# GasAlarm.net
KiCad netlist of a schematic drawn in EAGLE
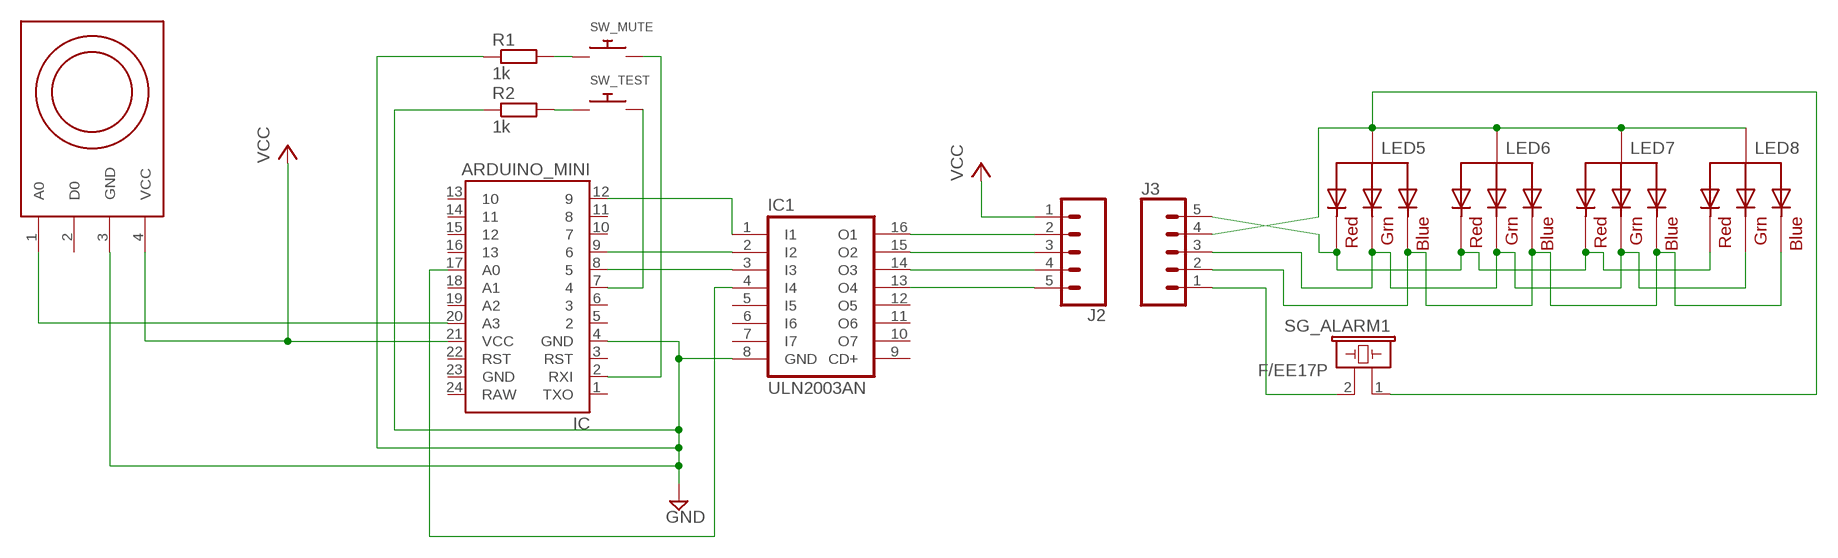
[diagram p0: schematic, sheet 1]

(export (version "E")
  (design (tool "Eeschema 10.0.6"))
  (components
    (comp (ref "IC")
      (value "ARDUINO_MINI")
      (footprint "eagle-import:ARDUINO_MINI")
      (libsource (lib "eagle-import") (part "ARDUINO_MINI"))
    )
    (comp (ref "IC1")
      (value "ULN2003AN")
      (footprint "eagle-import:DIL16")
      (libsource (lib "eagle-import") (part "ULN2003AN"))
    )
    (comp (ref "J2")
      (value "CONN_05")
      (footprint "eagle-import:1X05")
      (libsource (lib "eagle-import") (part "CONN_05"))
    )
    (comp (ref "J3")
      (value "CONN_05")
      (footprint "eagle-import:1X05")
      (libsource (lib "eagle-import") (part "CONN_05"))
    )
    (comp (ref "LED5")
      (value "RGBLED_CA-5MM")
      (footprint "eagle-import:LED5MMRGB")
      (libsource (lib "eagle-import") (part "RGBLED_CA-5MM"))
    )
    (comp (ref "LED6")
      (value "RGBLED_CA-5MM")
      (footprint "eagle-import:LED5MMRGB")
      (libsource (lib "eagle-import") (part "RGBLED_CA-5MM"))
    )
    (comp (ref "LED7")
      (value "RGBLED_CA-5MM")
      (footprint "eagle-import:LED5MMRGB")
      (libsource (lib "eagle-import") (part "RGBLED_CA-5MM"))
    )
    (comp (ref "LED8")
      (value "RGBLED_CA-5MM")
      (footprint "eagle-import:LED5MMRGB")
      (libsource (lib "eagle-import") (part "RGBLED_CA-5MM"))
    )
    (comp (ref "MQ6")
      (value "MQ-6")
      (footprint "eagle-import:DIP4-MQ_6")
      (libsource (lib "eagle-import") (part "MQ-6"))
    )
    (comp (ref "R1")
      (value "1k")
      (footprint "eagle-import:0204_5")
      (libsource (lib "eagle-import") (part "R-EU_0204/5"))
    )
    (comp (ref "R2")
      (value "1k")
      (footprint "eagle-import:0204_5")
      (libsource (lib "eagle-import") (part "R-EU_0204/5"))
    )
    (comp (ref "SG_ALARM1")
      (value "F/EE17P")
      (footprint "eagle-import:F_EE17P")
      (libsource (lib "eagle-import") (part "F/EE17P"))
    )
    (comp (ref "SW_MUTE")
      (value "SWITCH_PUSHBUTTONSOFTTOUCHSMD_SJ")
      (footprint "eagle-import:PUSHBUTTON_SMD_SJ")
      (libsource (lib "eagle-import") (part "SWITCH_PUSHBUTTONSOFTTOUCHSMD_SJ"))
    )
    (comp (ref "SW_TEST")
      (value "SWITCH_PUSHBUTTONSOFTTOUCHSMD_SJ")
      (footprint "eagle-import:PUSHBUTTON_SMD_SJ")
      (libsource (lib "eagle-import") (part "SWITCH_PUSHBUTTONSOFTTOUCHSMD_SJ"))
    )
  )
  (nets
    (net (code "1") (name "GND") (class "Default")
      (node (ref "IC") (pin "4") (pinfunction "GND_4") (pintype "bidirectional"))
      (node (ref "IC1") (pin "8") (pinfunction "GND_8") (pintype "power_in"))
      (node (ref "MQ6") (pin "3") (pinfunction "GND_3") (pintype "bidirectional"))
      (node (ref "R1") (pin "1") (pinfunction "1_1") (pintype "passive"))
      (node (ref "R2") (pin "1") (pinfunction "1_1") (pintype "passive"))
    )
    (net (code "2") (name "Net-(IC-4)") (class "Default")
      (node (ref "IC") (pin "7") (pinfunction "4_7") (pintype "bidirectional"))
      (node (ref "SW_TEST") (pin "P$2") (pinfunction "P$2_P$2") (pintype "passive"))
    )
    (net (code "3") (name "Net-(IC-5)") (class "Default")
      (node (ref "IC") (pin "8") (pinfunction "5_8") (pintype "bidirectional"))
      (node (ref "IC1") (pin "3") (pinfunction "I3_3") (pintype "input"))
    )
    (net (code "4") (name "Net-(IC-6)") (class "Default")
      (node (ref "IC") (pin "9") (pinfunction "6_9") (pintype "bidirectional"))
      (node (ref "IC1") (pin "2") (pinfunction "I2_2") (pintype "input"))
    )
    (net (code "5") (name "Net-(IC-9)") (class "Default")
      (node (ref "IC") (pin "12") (pinfunction "9_12") (pintype "bidirectional"))
      (node (ref "IC1") (pin "1") (pinfunction "I1_1") (pintype "input"))
    )
    (net (code "6") (name "Net-(IC-A0)") (class "Default")
      (node (ref "IC") (pin "17") (pinfunction "A0_17") (pintype "bidirectional"))
      (node (ref "IC1") (pin "4") (pinfunction "I4_4") (pintype "input"))
    )
    (net (code "7") (name "Net-(IC-A3)") (class "Default")
      (node (ref "IC") (pin "20") (pinfunction "A3_20") (pintype "bidirectional"))
      (node (ref "MQ6") (pin "1") (pinfunction "A0_1") (pintype "bidirectional"))
    )
    (net (code "8") (name "Net-(IC-RXI)") (class "Default")
      (node (ref "IC") (pin "2") (pinfunction "RXI_2") (pintype "bidirectional"))
      (node (ref "SW_MUTE") (pin "P$2") (pinfunction "P$2_P$2") (pintype "passive"))
    )
    (net (code "9") (name "Net-(IC1-O1)") (class "Default")
      (node (ref "IC1") (pin "16") (pinfunction "O1_16") (pintype "open_collector"))
      (node (ref "J2") (pin "2") (pinfunction "2_2") (pintype "passive"))
    )
    (net (code "10") (name "Net-(IC1-O2)") (class "Default")
      (node (ref "IC1") (pin "15") (pinfunction "O2_15") (pintype "open_collector"))
      (node (ref "J2") (pin "3") (pinfunction "3_3") (pintype "passive"))
    )
    (net (code "11") (name "Net-(IC1-O3)") (class "Default")
      (node (ref "IC1") (pin "14") (pinfunction "O3_14") (pintype "open_collector"))
      (node (ref "J2") (pin "4") (pinfunction "4_4") (pintype "passive"))
    )
    (net (code "12") (name "Net-(IC1-O4)") (class "Default")
      (node (ref "IC1") (pin "13") (pinfunction "O4_13") (pintype "open_collector"))
      (node (ref "J2") (pin "5") (pinfunction "5_5") (pintype "passive"))
    )
    (net (code "13") (name "Net-(J3-Pad1)") (class "Default")
      (node (ref "J3") (pin "1") (pinfunction "1_1") (pintype "passive"))
      (node (ref "SG_ALARM1") (pin "2") (pinfunction "2_2") (pintype "passive"))
    )
    (net (code "14") (name "Net-(LED5-BLUE)") (class "Default")
      (node (ref "J3") (pin "2") (pinfunction "2_2") (pintype "passive"))
      (node (ref "LED5") (pin "4") (pinfunction "BLUE_4") (pintype "bidirectional"))
      (node (ref "LED6") (pin "4") (pinfunction "BLUE_4") (pintype "bidirectional"))
      (node (ref "LED7") (pin "4") (pinfunction "BLUE_4") (pintype "bidirectional"))
      (node (ref "LED8") (pin "4") (pinfunction "BLUE_4") (pintype "bidirectional"))
    )
    (net (code "15") (name "Net-(LED5-GREEN)") (class "Default")
      (node (ref "J3") (pin "3") (pinfunction "3_3") (pintype "passive"))
      (node (ref "LED5") (pin "3") (pinfunction "GREEN_3") (pintype "bidirectional"))
      (node (ref "LED6") (pin "3") (pinfunction "GREEN_3") (pintype "bidirectional"))
      (node (ref "LED7") (pin "3") (pinfunction "GREEN_3") (pintype "bidirectional"))
      (node (ref "LED8") (pin "3") (pinfunction "GREEN_3") (pintype "bidirectional"))
    )
    (net (code "16") (name "Net-(LED5-RED)") (class "Default")
      (node (ref "J3") (pin "5") (pinfunction "5_5") (pintype "passive"))
      (node (ref "LED5") (pin "1") (pinfunction "RED_1") (pintype "bidirectional"))
      (node (ref "LED6") (pin "1") (pinfunction "RED_1") (pintype "bidirectional"))
      (node (ref "LED7") (pin "1") (pinfunction "RED_1") (pintype "bidirectional"))
      (node (ref "LED8") (pin "1") (pinfunction "RED_1") (pintype "bidirectional"))
    )
    (net (code "17") (name "Net-(LED5-VCC)") (class "Default")
      (node (ref "J3") (pin "4") (pinfunction "4_4") (pintype "passive"))
      (node (ref "LED5") (pin "2") (pinfunction "VCC_2") (pintype "bidirectional"))
      (node (ref "LED6") (pin "2") (pinfunction "VCC_2") (pintype "bidirectional"))
      (node (ref "LED7") (pin "2") (pinfunction "VCC_2") (pintype "bidirectional"))
      (node (ref "LED8") (pin "2") (pinfunction "VCC_2") (pintype "bidirectional"))
      (node (ref "SG_ALARM1") (pin "1") (pinfunction "1_1") (pintype "passive"))
    )
    (net (code "18") (name "Net-(R1-Pad2)") (class "Default")
      (node (ref "R1") (pin "2") (pinfunction "2_2") (pintype "passive"))
      (node (ref "SW_MUTE") (pin "P$1") (pinfunction "P$1_P$1") (pintype "passive"))
    )
    (net (code "19") (name "Net-(R2-Pad2)") (class "Default")
      (node (ref "R2") (pin "2") (pinfunction "2_2") (pintype "passive"))
      (node (ref "SW_TEST") (pin "P$1") (pinfunction "P$1_P$1") (pintype "passive"))
    )
    (net (code "20") (name "VCC") (class "Default")
      (node (ref "IC") (pin "21") (pinfunction "VCC_21") (pintype "bidirectional"))
      (node (ref "J2") (pin "1") (pinfunction "1_1") (pintype "passive"))
      (node (ref "MQ6") (pin "4") (pinfunction "VCC_4") (pintype "bidirectional"))
    )
    (net (code "21") (name "unconnected-(IC-2-Pad5)") (class "Default")
      (node (ref "IC") (pin "5") (pinfunction "2_5") (pintype "bidirectional"))
    )
    (net (code "22") (name "unconnected-(IC-3-Pad6)") (class "Default")
      (node (ref "IC") (pin "6") (pinfunction "3_6") (pintype "bidirectional"))
    )
    (net (code "23") (name "unconnected-(IC-7-Pad10)") (class "Default")
      (node (ref "IC") (pin "10") (pinfunction "7_10") (pintype "bidirectional"))
    )
    (net (code "24") (name "unconnected-(IC-8-Pad11)") (class "Default")
      (node (ref "IC") (pin "11") (pinfunction "8_11") (pintype "bidirectional"))
    )
    (net (code "25") (name "unconnected-(IC-10-Pad13)") (class "Default")
      (node (ref "IC") (pin "13") (pinfunction "10_13") (pintype "bidirectional"))
    )
    (net (code "26") (name "unconnected-(IC-11-Pad14)") (class "Default")
      (node (ref "IC") (pin "14") (pinfunction "11_14") (pintype "bidirectional"))
    )
    (net (code "27") (name "unconnected-(IC-12-Pad15)") (class "Default")
      (node (ref "IC") (pin "15") (pinfunction "12_15") (pintype "bidirectional"))
    )
    (net (code "28") (name "unconnected-(IC-13-Pad16)") (class "Default")
      (node (ref "IC") (pin "16") (pinfunction "13_16") (pintype "bidirectional"))
    )
    (net (code "29") (name "unconnected-(IC-A1-Pad18)") (class "Default")
      (node (ref "IC") (pin "18") (pinfunction "A1_18") (pintype "bidirectional"))
    )
    (net (code "30") (name "unconnected-(IC-A2-Pad19)") (class "Default")
      (node (ref "IC") (pin "19") (pinfunction "A2_19") (pintype "bidirectional"))
    )
    (net (code "31") (name "unconnected-(IC-GND-Pad23)") (class "Default")
      (node (ref "IC") (pin "23") (pinfunction "GND_23") (pintype "bidirectional"))
    )
    (net (code "32") (name "unconnected-(IC-RAW-Pad24)") (class "Default")
      (node (ref "IC") (pin "24") (pinfunction "RAW_24") (pintype "bidirectional"))
    )
    (net (code "33") (name "unconnected-(IC-RST-Pad3)") (class "Default")
      (node (ref "IC") (pin "3") (pinfunction "RST_3") (pintype "bidirectional"))
    )
    (net (code "34") (name "unconnected-(IC-RST-Pad22)") (class "Default")
      (node (ref "IC") (pin "22") (pinfunction "RST_22") (pintype "bidirectional"))
    )
    (net (code "35") (name "unconnected-(IC-TXO-Pad1)") (class "Default")
      (node (ref "IC") (pin "1") (pinfunction "TXO_1") (pintype "bidirectional"))
    )
    (net (code "36") (name "unconnected-(IC1-CD+-Pad9)") (class "Default")
      (node (ref "IC1") (pin "9") (pinfunction "CD+_9") (pintype "passive"))
    )
    (net (code "37") (name "unconnected-(IC1-I5-Pad5)") (class "Default")
      (node (ref "IC1") (pin "5") (pinfunction "I5_5") (pintype "input"))
    )
    (net (code "38") (name "unconnected-(IC1-I6-Pad6)") (class "Default")
      (node (ref "IC1") (pin "6") (pinfunction "I6_6") (pintype "input"))
    )
    (net (code "39") (name "unconnected-(IC1-I7-Pad7)") (class "Default")
      (node (ref "IC1") (pin "7") (pinfunction "I7_7") (pintype "input"))
    )
    (net (code "40") (name "unconnected-(IC1-O5-Pad12)") (class "Default")
      (node (ref "IC1") (pin "12") (pinfunction "O5_12") (pintype "open_collector"))
    )
    (net (code "41") (name "unconnected-(IC1-O6-Pad11)") (class "Default")
      (node (ref "IC1") (pin "11") (pinfunction "O6_11") (pintype "open_collector"))
    )
    (net (code "42") (name "unconnected-(IC1-O7-Pad10)") (class "Default")
      (node (ref "IC1") (pin "10") (pinfunction "O7_10") (pintype "open_collector"))
    )
    (net (code "43") (name "unconnected-(MQ6-D0-Pad2)") (class "Default")
      (node (ref "MQ6") (pin "2") (pinfunction "D0_2") (pintype "bidirectional"))
    )
  )
)
